# RN2483.net
KiCad netlist of a schematic drawn in Altium Designer
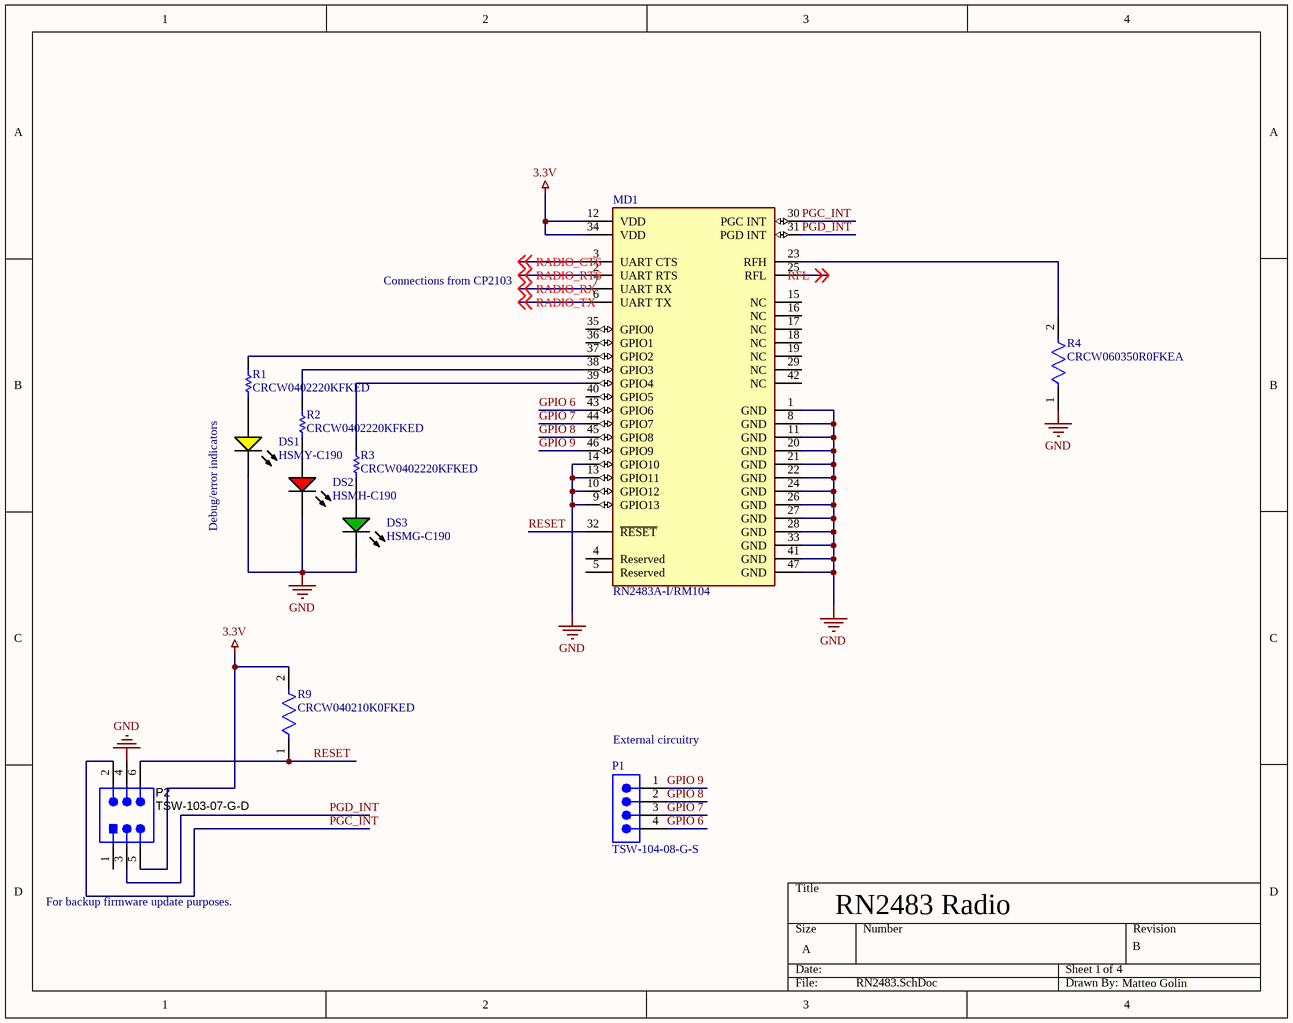
[diagram p0: RN2483.SchDoc]

(export (version "E")
  (design (tool "Eeschema 10.0.6"))
  (components
    (comp (ref "DS1")
      (value "HSMY-C190")
      (footprint "AVAG-HSMX-C190_V")
      (description "LED Uni-Color Yellow, 65 mW, 20 mA, -40 to 85 degC, 2-Pin SMD, RoHS, Tape and Reel")
      (fields (field (name "TOLERANCE") "1%"))
      (libsource (lib "Altium Content Vault") (part "LED-YELLOW-AK-2"))
    )
    (comp (ref "DS2")
      (value "HSMH-C190")
      (footprint "AVAG-HSMX-C190_V")
      (description "LED Uni-Color Red, 65 mW, 20 mA, -40 to 85 degC, 2-Pin SMD, RoHS, Tape and Reel")
      (libsource (lib "Altium Content Vault") (part "LED-RED-AK-2"))
    )
    (comp (ref "DS3")
      (value "HSMG-C190")
      (footprint "AVAG-HSMX-C190_V")
      (description "Chip LED, Green, 2.2 V, -40 to 85 degC, 2-Pin SMD, RoHS, Tape and Reel")
      (libsource (lib "Altium Content Vault") (part "LED-GREEN-AK-2"))
    )
    (comp (ref "MD1")
      (value "RN2483A-I/RM104")
      (footprint "FP-RN2483A-I-RM104-MFG")
      (fields
        (field (name "OCTOPART") "https://octopart.com/rn2483a-i%2Frm104-microchip-90584481")
        (field (name "MANUFACTURER") "Microchip")
      )
      (libsource (lib "Altium Content Vault") (part "630a5bff3a952dd521c0edb04079da7"))
    )
    (comp (ref "P1")
      (value "TSW-104-08-G-S")
      (footprint "SMTC-TSW-104-08-X-S")
      (description "0.025\" SQ Post Header, Through-hole, Vertical, -55 to 125 degC, 2.54 mm Pitch, 4-Pin, Male, RoHS")
      (fields (field (name "MANUFACTURER") "Samtec"))
      (libsource (lib "Altium Content Vault") (part "SMTC-TSW-104-08-X-S"))
    )
    (comp (ref "P2")
      (value "TSW-103-07-G-D")
      (footprint "SMTC-TSW-103-07-G-D_V")
      (fields (field (name "MANUFACTURER") "Samtec-Inc."))
      (libsource (lib "Altium Content Vault") (part "CN-2P-M-R6"))
    )
    (comp (ref "R1")
      (value "CRCW0402220KFKED")
      (footprint "RESC1005X40X25LL05T05")
      (fields (field (name "MANUFACTURER") "Vishay Dale"))
      (libsource (lib "Altium Content Vault") (part "RES"))
    )
    (comp (ref "R2")
      (value "CRCW0402220KFKED")
      (footprint "RESC1005X40X25LL05T05")
      (fields (field (name "MANUFACTURER") "Vishay Dale"))
      (libsource (lib "Altium Content Vault") (part "RES"))
    )
    (comp (ref "R3")
      (value "CRCW0402220KFKED")
      (footprint "RESC1005X40X25LL05T05")
      (fields (field (name "MANUFACTURER") "Vishay Dale"))
      (libsource (lib "Altium Content Vault") (part "RES"))
    )
    (comp (ref "R4")
      (value "CRCW060350R0FKEA")
      (footprint "FP-CRCW0603-e3-MFG")
      (description "RES Thick Film, 50Ω, 1%, 0.1W, 100ppm/°C, 0603")
      (fields (field (name "TOLERANCE") "1%"))
      (libsource (lib "Altium Content Vault") (part "1029c3af85768c4190bb7ad29bc67b5"))
    )
    (comp (ref "R9")
      (value "CRCW040210K0FKED")
      (footprint "FP-CRCW0402-e3-IPC_B")
      (description "RES SMD 10K OHM 1% 1/16W 0402")
      (fields (field (name "TOLERANCE") "1%"))
      (libsource (lib "Altium Content Vault") (part "1029c3af85768c4190bb7ad29bc67b5"))
    )
  )
  (nets
    (net (code "1") (name "/GPIO 6") (class "Default")
      (node (ref "MD1") (pin "43") (pinfunction "GPIO6_43") (pintype "bidirectional"))
      (node (ref "P1") (pin "4") (pinfunction "4_4") (pintype "passive"))
    )
    (net (code "2") (name "/GPIO 7") (class "Default")
      (node (ref "MD1") (pin "44") (pinfunction "GPIO7_44") (pintype "bidirectional"))
      (node (ref "P1") (pin "3") (pinfunction "3_3") (pintype "passive"))
    )
    (net (code "3") (name "/GPIO 8") (class "Default")
      (node (ref "MD1") (pin "45") (pinfunction "GPIO8_45") (pintype "bidirectional"))
      (node (ref "P1") (pin "2") (pinfunction "2_2") (pintype "passive"))
    )
    (net (code "4") (name "/GPIO 9") (class "Default")
      (node (ref "MD1") (pin "46") (pinfunction "GPIO9_46") (pintype "bidirectional"))
      (node (ref "P1") (pin "1") (pinfunction "1_1") (pintype "passive"))
    )
    (net (code "5") (name "/PGC_INT") (class "Default")
      (node (ref "MD1") (pin "30") (pinfunction "PGC_INT_30") (pintype "bidirectional"))
      (node (ref "P2") (pin "2") (pinfunction "2_2") (pintype "passive"))
    )
    (net (code "6") (name "/PGD_INT") (class "Default")
      (node (ref "MD1") (pin "31") (pinfunction "PGD_INT_31") (pintype "bidirectional"))
      (node (ref "P2") (pin "3") (pinfunction "3_3") (pintype "passive"))
    )
    (net (code "7") (name "/RESET") (class "Default")
      (node (ref "MD1") (pin "32") (pinfunction "~{RESET}_32") (pintype "passive"))
      (node (ref "P2") (pin "6") (pinfunction "6_6") (pintype "passive"))
      (node (ref "R9") (pin "1") (pinfunction "1_1") (pintype "passive"))
    )
    (net (code "8") (name "3.3V") (class "Default")
      (node (ref "MD1") (pin "12") (pinfunction "VDD_12") (pintype "passive"))
      (node (ref "MD1") (pin "34") (pinfunction "VDD_34") (pintype "passive"))
      (node (ref "P2") (pin "5") (pinfunction "5_5") (pintype "passive"))
      (node (ref "R9") (pin "2") (pinfunction "2_2") (pintype "passive"))
    )
    (net (code "9") (name "GND") (class "Default")
      (node (ref "DS1") (pin "2") (pinfunction "K_2") (pintype "passive"))
      (node (ref "DS2") (pin "2") (pinfunction "K_2") (pintype "passive"))
      (node (ref "DS3") (pin "2") (pinfunction "K_2") (pintype "passive"))
      (node (ref "MD1") (pin "1") (pinfunction "GND_1") (pintype "passive"))
      (node (ref "MD1") (pin "10") (pinfunction "GPIO12_10") (pintype "bidirectional"))
      (node (ref "MD1") (pin "11") (pinfunction "GND_11") (pintype "passive"))
      (node (ref "MD1") (pin "13") (pinfunction "GPIO11_13") (pintype "bidirectional"))
      (node (ref "MD1") (pin "14") (pinfunction "GPIO10_14") (pintype "bidirectional"))
      (node (ref "MD1") (pin "20") (pinfunction "GND_20") (pintype "passive"))
      (node (ref "MD1") (pin "21") (pinfunction "GND_21") (pintype "passive"))
      (node (ref "MD1") (pin "22") (pinfunction "GND_22") (pintype "passive"))
      (node (ref "MD1") (pin "24") (pinfunction "GND_24") (pintype "passive"))
      (node (ref "MD1") (pin "26") (pinfunction "GND_26") (pintype "passive"))
      (node (ref "MD1") (pin "27") (pinfunction "GND_27") (pintype "passive"))
      (node (ref "MD1") (pin "28") (pinfunction "GND_28") (pintype "passive"))
      (node (ref "MD1") (pin "33") (pinfunction "GND_33") (pintype "passive"))
      (node (ref "MD1") (pin "41") (pinfunction "GND_41") (pintype "passive"))
      (node (ref "MD1") (pin "47") (pinfunction "GND_47") (pintype "passive"))
      (node (ref "MD1") (pin "8") (pinfunction "GND_8") (pintype "passive"))
      (node (ref "MD1") (pin "9") (pinfunction "GPIO13_9") (pintype "bidirectional"))
      (node (ref "P2") (pin "4") (pinfunction "4_4") (pintype "passive"))
      (node (ref "R4") (pin "1") (pinfunction "1_1") (pintype "passive"))
    )
    (net (code "10") (name "Net-(DS1-A)") (class "Default")
      (node (ref "DS1") (pin "1") (pinfunction "A_1") (pintype "passive"))
      (node (ref "R1") (pin "1") (pinfunction "1_1") (pintype "passive"))
    )
    (net (code "11") (name "Net-(DS2-A)") (class "Default")
      (node (ref "DS2") (pin "1") (pinfunction "A_1") (pintype "passive"))
      (node (ref "R2") (pin "1") (pinfunction "1_1") (pintype "passive"))
    )
    (net (code "12") (name "Net-(DS3-A)") (class "Default")
      (node (ref "DS3") (pin "1") (pinfunction "A_1") (pintype "passive"))
      (node (ref "R3") (pin "1") (pinfunction "1_1") (pintype "passive"))
    )
    (net (code "13") (name "Net-(MD1-GPIO2)") (class "Default")
      (node (ref "MD1") (pin "37") (pinfunction "GPIO2_37") (pintype "bidirectional"))
      (node (ref "R1") (pin "2") (pinfunction "2_2") (pintype "passive"))
    )
    (net (code "14") (name "Net-(MD1-GPIO3)") (class "Default")
      (node (ref "MD1") (pin "38") (pinfunction "GPIO3_38") (pintype "bidirectional"))
      (node (ref "R2") (pin "2") (pinfunction "2_2") (pintype "passive"))
    )
    (net (code "15") (name "Net-(MD1-GPIO4)") (class "Default")
      (node (ref "MD1") (pin "39") (pinfunction "GPIO4_39") (pintype "bidirectional"))
      (node (ref "R3") (pin "2") (pinfunction "2_2") (pintype "passive"))
    )
    (net (code "16") (name "Net-(MD1-RFH)") (class "Default")
      (node (ref "MD1") (pin "23") (pinfunction "RFH_23") (pintype "passive"))
      (node (ref "R4") (pin "2") (pinfunction "2_2") (pintype "passive"))
    )
    (net (code "17") (name "RADIO_CTS") (class "Default")
      (node (ref "MD1") (pin "3") (pinfunction "UART_CTS_3") (pintype "passive"))
    )
    (net (code "18") (name "RADIO_RTS") (class "Default")
      (node (ref "MD1") (pin "2") (pinfunction "UART_RTS_2") (pintype "passive"))
    )
    (net (code "19") (name "RADIO_RX") (class "Default")
      (node (ref "MD1") (pin "7") (pinfunction "UART_RX_7") (pintype "passive"))
    )
    (net (code "20") (name "RADIO_TX") (class "Default")
      (node (ref "MD1") (pin "6") (pinfunction "UART_TX_6") (pintype "passive"))
    )
    (net (code "21") (name "RFL") (class "Default")
      (node (ref "MD1") (pin "25") (pinfunction "RFL_25") (pintype "passive"))
    )
    (net (code "22") (name "unconnected-(MD1-GPIO0-Pad35)") (class "Default")
      (node (ref "MD1") (pin "35") (pinfunction "GPIO0_35") (pintype "bidirectional"))
    )
    (net (code "23") (name "unconnected-(MD1-GPIO1-Pad36)") (class "Default")
      (node (ref "MD1") (pin "36") (pinfunction "GPIO1_36") (pintype "bidirectional"))
    )
    (net (code "24") (name "unconnected-(MD1-GPIO5-Pad40)") (class "Default")
      (node (ref "MD1") (pin "40") (pinfunction "GPIO5_40") (pintype "bidirectional"))
    )
    (net (code "25") (name "unconnected-(MD1-NC-Pad15)") (class "Default")
      (node (ref "MD1") (pin "15") (pinfunction "NC_15") (pintype "passive"))
    )
    (net (code "26") (name "unconnected-(MD1-NC-Pad16)") (class "Default")
      (node (ref "MD1") (pin "16") (pinfunction "NC_16") (pintype "passive"))
    )
    (net (code "27") (name "unconnected-(MD1-NC-Pad17)") (class "Default")
      (node (ref "MD1") (pin "17") (pinfunction "NC_17") (pintype "passive"))
    )
    (net (code "28") (name "unconnected-(MD1-NC-Pad18)") (class "Default")
      (node (ref "MD1") (pin "18") (pinfunction "NC_18") (pintype "passive"))
    )
    (net (code "29") (name "unconnected-(MD1-NC-Pad19)") (class "Default")
      (node (ref "MD1") (pin "19") (pinfunction "NC_19") (pintype "passive"))
    )
    (net (code "30") (name "unconnected-(MD1-NC-Pad29)") (class "Default")
      (node (ref "MD1") (pin "29") (pinfunction "NC_29") (pintype "passive"))
    )
    (net (code "31") (name "unconnected-(MD1-NC-Pad42)") (class "Default")
      (node (ref "MD1") (pin "42") (pinfunction "NC_42") (pintype "passive"))
    )
    (net (code "32") (name "unconnected-(MD1-Reserved-Pad4)") (class "Default")
      (node (ref "MD1") (pin "4") (pinfunction "Reserved_4") (pintype "passive"))
    )
    (net (code "33") (name "unconnected-(MD1-Reserved-Pad5)") (class "Default")
      (node (ref "MD1") (pin "5") (pinfunction "Reserved_5") (pintype "passive"))
    )
    (net (code "34") (name "unconnected-(P2-Pad1)") (class "Default")
      (node (ref "P2") (pin "1") (pinfunction "1_1") (pintype "passive"))
    )
  )
)
